# M3_FMCW.net
KiCad netlist of a schematic drawn in Altium Designer
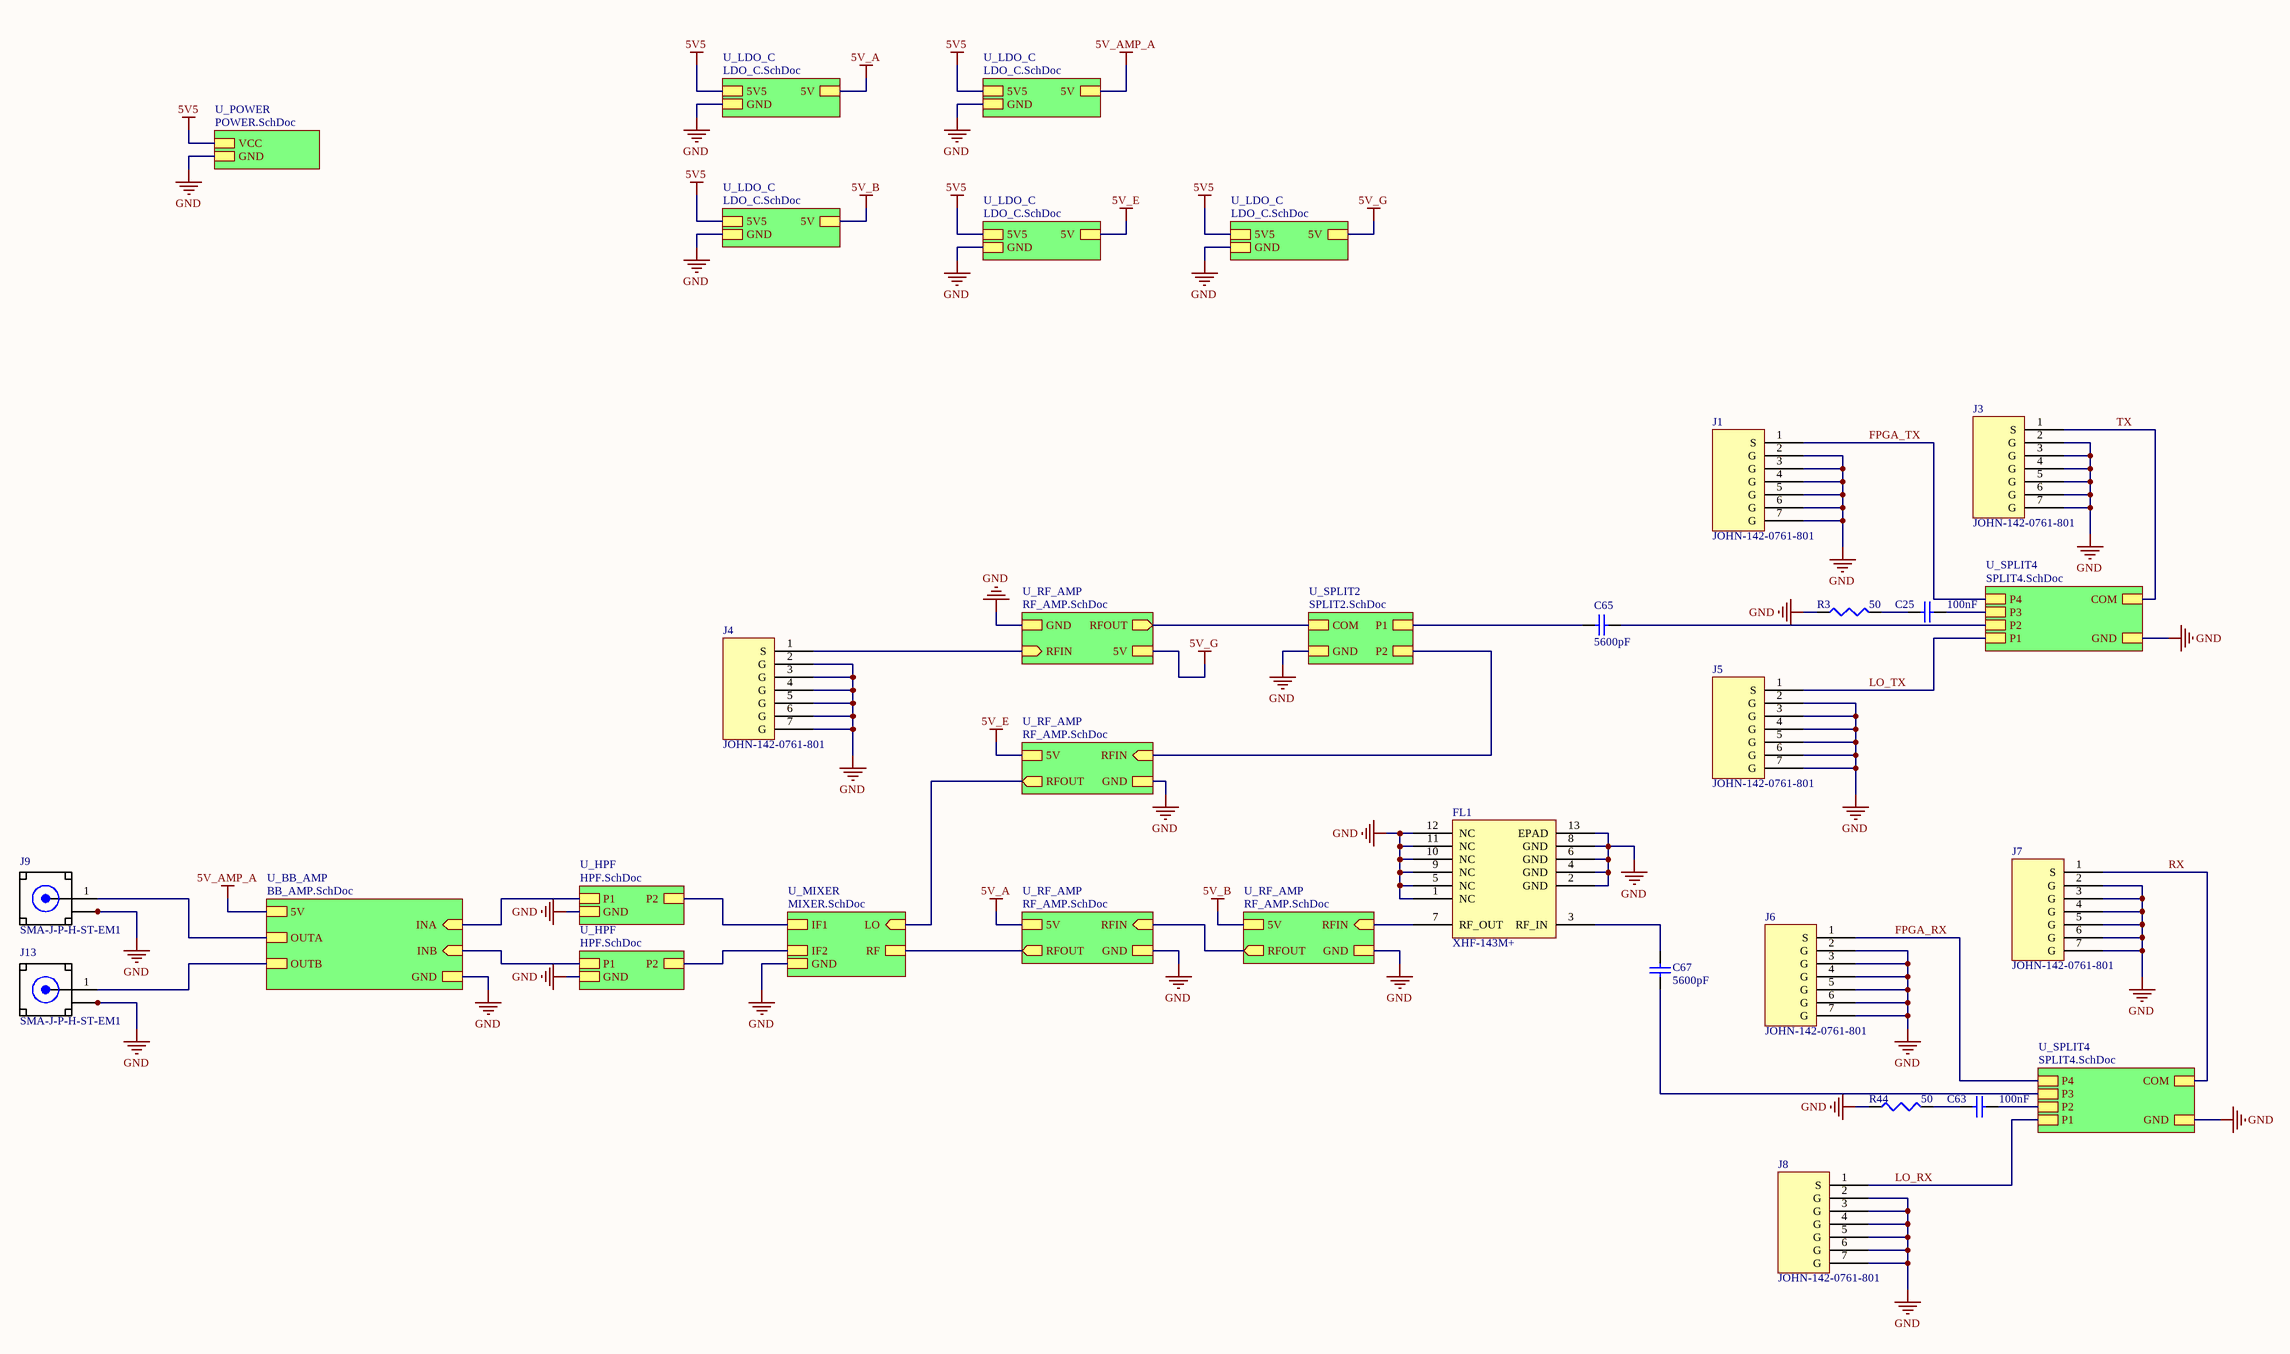
[diagram p0: M3_FMCW.SchDoc]

(export (version "E")
  (design (tool "Eeschema 10.0.6"))
  (components
    (comp (ref "C25")
      (value "100nF")
      (footprint "SMD-0402")
      (description "Broadband Ceramic Capacitor X7R 0402 (1005 Metric)")
      (libsource (lib "LCR") (part "CAP_RF_0402"))
    )
    (comp (ref "C63")
      (value "100nF")
      (footprint "SMD-0402")
      (description "Broadband Ceramic Capacitor X7R 0402 (1005 Metric)")
      (libsource (lib "LCR") (part "CAP_RF_0402"))
    )
    (comp (ref "C65")
      (value "5600pF")
      (footprint "Johanson-0201")
      (description "Broadband Capacitor 0201 Imperial")
      (libsource (lib "LCR") (part "CAP_RF_0201"))
    )
    (comp (ref "C67")
      (value "5600pF")
      (footprint "Johanson-0201")
      (description "Broadband Capacitor 0201 Imperial")
      (libsource (lib "LCR") (part "CAP_RF_0201"))
    )
    (comp (ref "FL1")
      (value "XHF-143M+")
      (footprint "PQFN12-XHF-143M")
      (description "Reflectionless High Pass Filter 50Ω 13900 to19000 MHz")
      (libsource (lib "FullyDigital") (part "XHF-143M+"))
    )
    (comp (ref "J1")
      (value "JOHN-142-0761-801")
      (footprint "JOHN-142-0761-801")
      (description "CONN SMA JACK STR 50OHM EDGE MNT")
      (libsource (lib "Connectors") (part "JOHN-142-0761-801"))
    )
    (comp (ref "J3")
      (value "JOHN-142-0761-801")
      (footprint "JOHN-142-0761-801")
      (description "CONN SMA JACK STR 50OHM EDGE MNT")
      (libsource (lib "Connectors") (part "JOHN-142-0761-801"))
    )
    (comp (ref "J4")
      (value "JOHN-142-0761-801")
      (footprint "JOHN-142-0761-801")
      (description "CONN SMA JACK STR 50OHM EDGE MNT")
      (libsource (lib "Connectors") (part "JOHN-142-0761-801"))
    )
    (comp (ref "J5")
      (value "JOHN-142-0761-801")
      (footprint "JOHN-142-0761-801")
      (description "CONN SMA JACK STR 50OHM EDGE MNT")
      (libsource (lib "Connectors") (part "JOHN-142-0761-801"))
    )
    (comp (ref "J6")
      (value "JOHN-142-0761-801")
      (footprint "JOHN-142-0761-801")
      (description "CONN SMA JACK STR 50OHM EDGE MNT")
      (libsource (lib "Connectors") (part "JOHN-142-0761-801"))
    )
    (comp (ref "J7")
      (value "JOHN-142-0761-801")
      (footprint "JOHN-142-0761-801")
      (description "CONN SMA JACK STR 50OHM EDGE MNT")
      (libsource (lib "Connectors") (part "JOHN-142-0761-801"))
    )
    (comp (ref "J8")
      (value "JOHN-142-0761-801")
      (footprint "JOHN-142-0761-801")
      (description "CONN SMA JACK STR 50OHM EDGE MNT")
      (libsource (lib "Connectors") (part "JOHN-142-0761-801"))
    )
    (comp (ref "J9")
      (value "SMA-J-P-H-ST-EM1")
      (footprint "SMA-J-P-H-ST-EM1")
      (description "Connector SMA F 50Ohm Solder ST Edge Mount Gold Over Nickel Tray")
      (fields (field (name "MF") "Samtec"))
      (libsource (lib "Connectors") (part "SMA-J-P-H-ST-EM1"))
    )
    (comp (ref "J13")
      (value "SMA-J-P-H-ST-EM1")
      (footprint "SMA-J-P-H-ST-EM1")
      (description "Connector SMA F 50Ohm Solder ST Edge Mount Gold Over Nickel Tray")
      (fields (field (name "MF") "Samtec"))
      (libsource (lib "Connectors") (part "SMA-J-P-H-ST-EM1"))
    )
    (comp (ref "R3")
      (value "50")
      (footprint "SMD-0402")
      (description "High Frequency Resistor 0402")
      (libsource (lib "LCR") (part "RES_RF_0402"))
    )
    (comp (ref "R44")
      (value "50")
      (footprint "SMD-0402")
      (description "High Frequency Resistor 0402")
      (libsource (lib "LCR") (part "RES_RF_0402"))
    )
  )
  (nets
    (net (code "1") (name "/FPGA_RX") (class "Default")
      (node (ref "J6") (pin "1") (pinfunction "S_1") (pintype "passive"))
    )
    (net (code "2") (name "/FPGA_TX") (class "Default")
      (node (ref "J1") (pin "1") (pinfunction "S_1") (pintype "passive"))
    )
    (net (code "7") (name "/LO_RX") (class "Default")
      (node (ref "J8") (pin "1") (pinfunction "S_1") (pintype "passive"))
    )
    (net (code "8") (name "/LO_TX") (class "Default")
      (node (ref "J5") (pin "1") (pinfunction "S_1") (pintype "passive"))
    )
    (net (code "9") (name "/OUTA") (class "Default")
      (node (ref "J9") (pin "1") (pinfunction "SIGNAL_1") (pintype "passive"))
    )
    (net (code "10") (name "/OUTB") (class "Default")
      (node (ref "J13") (pin "1") (pinfunction "SIGNAL_1") (pintype "passive"))
    )
    (net (code "11") (name "/P1") (class "Default")
      (node (ref "C65") (pin "2") (pinfunction "2_2") (pintype "passive"))
    )
    (net (code "12") (name "/P2") (class "Default")
      (node (ref "C63") (pin "2") (pinfunction "2_2") (pintype "passive"))
    )
    (net (code "14") (name "/P2_2") (class "Default")
      (node (ref "C65") (pin "1") (pinfunction "1_1") (pintype "passive"))
    )
    (net (code "15") (name "/P3") (class "Default")
      (node (ref "C25") (pin "2") (pinfunction "2_2") (pintype "passive"))
    )
    (net (code "16") (name "/P3_1") (class "Default")
      (node (ref "C67") (pin "1") (pinfunction "1_1") (pintype "passive"))
    )
    (net (code "17") (name "/RFIN") (class "Default")
      (node (ref "J4") (pin "1") (pinfunction "S_1") (pintype "passive"))
    )
    (net (code "18") (name "/RFIN_1") (class "Default")
      (node (ref "FL1") (pin "7") (pinfunction "RF_OUT_7") (pintype "passive"))
    )
    (net (code "23") (name "/RX") (class "Default")
      (node (ref "J7") (pin "1") (pinfunction "S_1") (pintype "passive"))
    )
    (net (code "24") (name "/TX") (class "Default")
      (node (ref "J3") (pin "1") (pinfunction "S_1") (pintype "passive"))
    )
    (net (code "31") (name "GND") (class "Default")
      (node (ref "FL1") (pin "1") (pinfunction "NC_1") (pintype "passive"))
      (node (ref "FL1") (pin "10") (pinfunction "NC_10") (pintype "passive"))
      (node (ref "FL1") (pin "11") (pinfunction "NC_11") (pintype "passive"))
      (node (ref "FL1") (pin "12") (pinfunction "NC_12") (pintype "passive"))
      (node (ref "FL1") (pin "13") (pinfunction "EPAD_13") (pintype "passive"))
      (node (ref "FL1") (pin "2") (pinfunction "GND_2") (pintype "passive"))
      (node (ref "FL1") (pin "4") (pinfunction "GND_4") (pintype "passive"))
      (node (ref "FL1") (pin "5") (pinfunction "NC_5") (pintype "passive"))
      (node (ref "FL1") (pin "6") (pinfunction "GND_6") (pintype "passive"))
      (node (ref "FL1") (pin "8") (pinfunction "GND_8") (pintype "passive"))
      (node (ref "FL1") (pin "9") (pinfunction "NC_9") (pintype "passive"))
      (node (ref "J1") (pin "2") (pinfunction "G_2") (pintype "passive"))
      (node (ref "J1") (pin "3") (pinfunction "G_3") (pintype "passive"))
      (node (ref "J1") (pin "4") (pinfunction "G_4") (pintype "passive"))
      (node (ref "J1") (pin "5") (pinfunction "G_5") (pintype "passive"))
      (node (ref "J1") (pin "6") (pinfunction "G_6") (pintype "passive"))
      (node (ref "J1") (pin "7") (pinfunction "G_7") (pintype "passive"))
      (node (ref "J13") (pin "2_1") (pinfunction "GND_2_1") (pintype "power_in"))
      (node (ref "J13") (pin "2_2") (pinfunction "GND_2_2") (pintype "power_in"))
      (node (ref "J13") (pin "3_1") (pinfunction "GND_3_1") (pintype "power_in"))
      (node (ref "J13") (pin "3_2") (pinfunction "GND_3_2") (pintype "power_in"))
      (node (ref "J3") (pin "2") (pinfunction "G_2") (pintype "passive"))
      (node (ref "J3") (pin "3") (pinfunction "G_3") (pintype "passive"))
      (node (ref "J3") (pin "4") (pinfunction "G_4") (pintype "passive"))
      (node (ref "J3") (pin "5") (pinfunction "G_5") (pintype "passive"))
      (node (ref "J3") (pin "6") (pinfunction "G_6") (pintype "passive"))
      (node (ref "J3") (pin "7") (pinfunction "G_7") (pintype "passive"))
      (node (ref "J4") (pin "2") (pinfunction "G_2") (pintype "passive"))
      (node (ref "J4") (pin "3") (pinfunction "G_3") (pintype "passive"))
      (node (ref "J4") (pin "4") (pinfunction "G_4") (pintype "passive"))
      (node (ref "J4") (pin "5") (pinfunction "G_5") (pintype "passive"))
      (node (ref "J4") (pin "6") (pinfunction "G_6") (pintype "passive"))
      (node (ref "J4") (pin "7") (pinfunction "G_7") (pintype "passive"))
      (node (ref "J5") (pin "2") (pinfunction "G_2") (pintype "passive"))
      (node (ref "J5") (pin "3") (pinfunction "G_3") (pintype "passive"))
      (node (ref "J5") (pin "4") (pinfunction "G_4") (pintype "passive"))
      (node (ref "J5") (pin "5") (pinfunction "G_5") (pintype "passive"))
      (node (ref "J5") (pin "6") (pinfunction "G_6") (pintype "passive"))
      (node (ref "J5") (pin "7") (pinfunction "G_7") (pintype "passive"))
      (node (ref "J6") (pin "2") (pinfunction "G_2") (pintype "passive"))
      (node (ref "J6") (pin "3") (pinfunction "G_3") (pintype "passive"))
      (node (ref "J6") (pin "4") (pinfunction "G_4") (pintype "passive"))
      (node (ref "J6") (pin "5") (pinfunction "G_5") (pintype "passive"))
      (node (ref "J6") (pin "6") (pinfunction "G_6") (pintype "passive"))
      (node (ref "J6") (pin "7") (pinfunction "G_7") (pintype "passive"))
      (node (ref "J7") (pin "2") (pinfunction "G_2") (pintype "passive"))
      (node (ref "J7") (pin "3") (pinfunction "G_3") (pintype "passive"))
      (node (ref "J7") (pin "4") (pinfunction "G_4") (pintype "passive"))
      (node (ref "J7") (pin "5") (pinfunction "G_5") (pintype "passive"))
      (node (ref "J7") (pin "6") (pinfunction "G_6") (pintype "passive"))
      (node (ref "J7") (pin "7") (pinfunction "G_7") (pintype "passive"))
      (node (ref "J8") (pin "2") (pinfunction "G_2") (pintype "passive"))
      (node (ref "J8") (pin "3") (pinfunction "G_3") (pintype "passive"))
      (node (ref "J8") (pin "4") (pinfunction "G_4") (pintype "passive"))
      (node (ref "J8") (pin "5") (pinfunction "G_5") (pintype "passive"))
      (node (ref "J8") (pin "6") (pinfunction "G_6") (pintype "passive"))
      (node (ref "J8") (pin "7") (pinfunction "G_7") (pintype "passive"))
      (node (ref "J9") (pin "2_1") (pinfunction "GND_2_1") (pintype "power_in"))
      (node (ref "J9") (pin "2_2") (pinfunction "GND_2_2") (pintype "power_in"))
      (node (ref "J9") (pin "3_1") (pinfunction "GND_3_1") (pintype "power_in"))
      (node (ref "J9") (pin "3_2") (pinfunction "GND_3_2") (pintype "power_in"))
      (node (ref "R3") (pin "1") (pinfunction "1_1") (pintype "passive"))
      (node (ref "R44") (pin "1") (pinfunction "1_1") (pintype "passive"))
    )
    (net (code "32") (name "Net-(C25-Pad1)") (class "Default")
      (node (ref "C25") (pin "1") (pinfunction "1_1") (pintype "passive"))
      (node (ref "R3") (pin "2") (pinfunction "2_2") (pintype "passive"))
    )
    (net (code "33") (name "Net-(C63-Pad1)") (class "Default")
      (node (ref "C63") (pin "1") (pinfunction "1_1") (pintype "passive"))
      (node (ref "R44") (pin "2") (pinfunction "2_2") (pintype "passive"))
    )
    (net (code "34") (name "Net-(FL1-RF_IN)") (class "Default")
      (node (ref "C67") (pin "2") (pinfunction "2_2") (pintype "passive"))
      (node (ref "FL1") (pin "3") (pinfunction "RF_IN_3") (pintype "passive"))
    )
  )
)
